# Ikea_Environmental_Sensor.net
KiCad netlist of a schematic drawn in Altium Designer
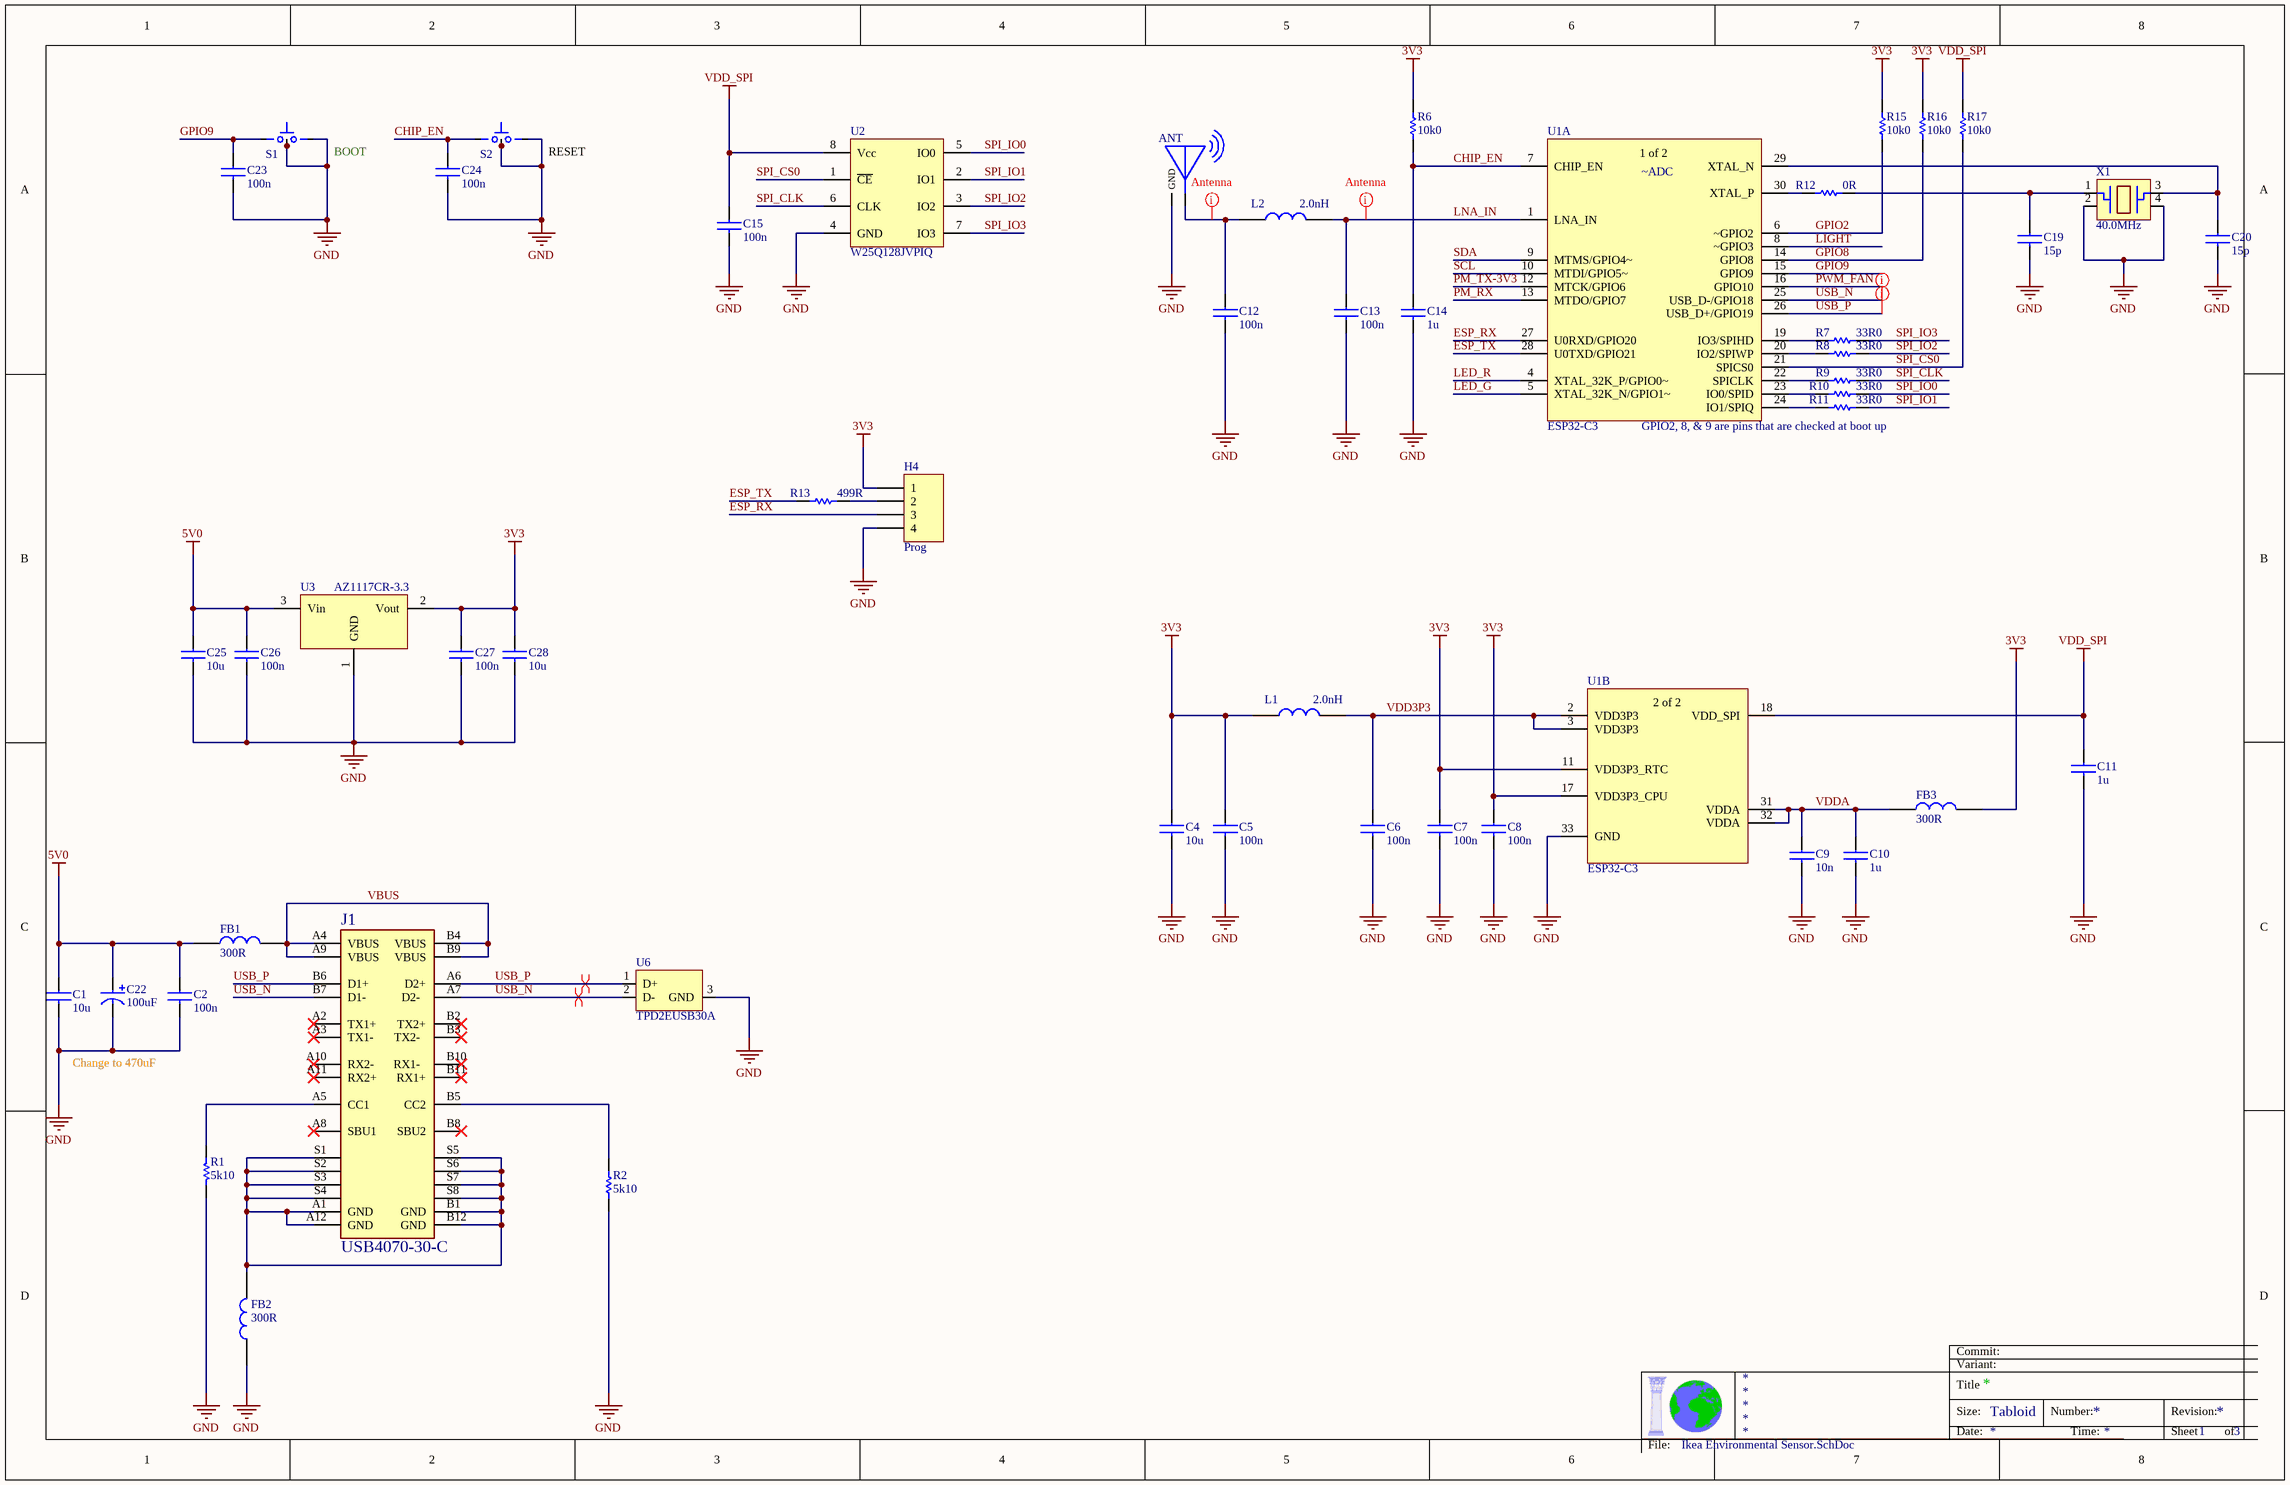
[diagram p0: Ikea Environmental Sensor.SchDoc]

(export (version "E")
  (design (tool "Eeschema 10.0.6"))
  (components
    (comp (ref "ANT")
      (value "PCB Antenna")
      (footprint "MINI-ANT-TYPED-H - Flipped")
      (description "Antenna MIFA 2.4Gig")
      (fields (field (name "MANUFACTURER") "Rainsun") (field (name "LCSC_PART_NUMBER") "C99665"))
      (libsource (lib "GLIB") (part "Antenna_PCB_MIFA"))
    )
    (comp (ref "C1")
      (value "10u")
      (footprint "0603X90")
      (description "Cap, Chip, 10uF, 10V, ± 15%, X5R, 0603")
      (fields (field (name "MANUFACTURER") "NIC") (field (name "JLCPCB_PART_#") "C96446"))
      (libsource (lib "GLIB") (part "C_10u_10V_10_0603_NIC"))
    )
    (comp (ref "C2")
      (value "100n")
      (footprint "C_0402_N")
      (description "Cap, Chip, 100nF, 16V, +/-10%, X7R, 0402")
      (fields (field (name "MANUFACTURER") "NIC") (field (name "JLCPCB_PART_#") "C307331"))
      (libsource (lib "GLIB") (part "C_100n_16V_10_0402_NIC"))
    )
    (comp (ref "C4")
      (value "10u")
      (footprint "0603X90")
      (description "Cap, Chip, 10uF, 10V, ± 15%, X5R, 0603")
      (fields (field (name "MANUFACTURER") "NIC"))
      (libsource (lib "GLIB") (part "C_10u_10V_10_0603_NIC"))
    )
    (comp (ref "C5")
      (value "100n")
      (footprint "C_0402_N")
      (description "Cap, Chip, 100nF, 16V, +/-10%, X7R, 0402")
      (fields (field (name "MANUFACTURER") "NIC"))
      (libsource (lib "GLIB") (part "C_100n_16V_10_0402_NIC"))
    )
    (comp (ref "C6")
      (value "100n")
      (footprint "C_0402_N")
      (description "Cap, Chip, 100nF, 16V, +/-10%, X7R, 0402")
      (fields (field (name "MANUFACTURER") "NIC"))
      (libsource (lib "GLIB") (part "C_100n_16V_10_0402_NIC"))
    )
    (comp (ref "C7")
      (value "100n")
      (footprint "C_0402_N")
      (description "Cap, Chip, 100nF, 16V, +/-10%, X7R, 0402")
      (fields (field (name "MANUFACTURER") "NIC"))
      (libsource (lib "GLIB") (part "C_100n_16V_10_0402_NIC"))
    )
    (comp (ref "C8")
      (value "100n")
      (footprint "C_0402_N")
      (description "Cap, Chip, 100nF, 16V, +/-10%, X7R, 0402")
      (fields (field (name "MANUFACTURER") "NIC"))
      (libsource (lib "GLIB") (part "C_100n_16V_10_0402_NIC"))
    )
    (comp (ref "C9")
      (value "10n")
      (footprint "C_0402_N")
      (description "Cap, Chip, 0.01uF, 25V, 20%, X7R, 0402")
      (fields (field (name "MANUFACTURER") "NIC"))
      (libsource (lib "GLIB") (part "C_10n_25V_20_0402_NIC"))
    )
    (comp (ref "C10")
      (value "1u")
      (footprint "C_0402_N")
      (description "Cap, Chip, 1uF, 10V, 10%, X5R, 0402")
      (fields (field (name "MANUFACTURER") "NIC"))
      (libsource (lib "GLIB") (part "C_1u_10V_10_0402_NIC"))
    )
    (comp (ref "C11")
      (value "1u")
      (footprint "C_0402_N")
      (description "Cap, Chip, 1uF, 10V, 10%, X5R, 0402")
      (fields (field (name "MANUFACTURER") "NIC"))
      (libsource (lib "GLIB") (part "C_1u_10V_10_0402_NIC"))
    )
    (comp (ref "C12")
      (value "100n")
      (footprint "C_0201")
      (description "Cap, Chip, 100nF, 25V, +/-10%, X5R, 0201")
      (fields (field (name "MANUFACTURER") "Murata"))
      (libsource (lib "GLIB") (part "C_100n_25V_10_0201_Murata"))
    )
    (comp (ref "C13")
      (value "100n")
      (footprint "C_0201")
      (description "Cap, Chip, 100nF, 25V, +/-10%, X5R, 0201")
      (fields (field (name "MANUFACTURER") "Murata"))
      (libsource (lib "GLIB") (part "C_100n_25V_10_0201_Murata"))
    )
    (comp (ref "C14")
      (value "1u")
      (footprint "C_0402_N")
      (description "Cap, Chip, 1uF, 10V, 10%, X5R, 0402")
      (fields (field (name "MANUFACTURER") "NIC"))
      (libsource (lib "GLIB") (part "C_1u_10V_10_0402_NIC"))
    )
    (comp (ref "C15")
      (value "100n")
      (footprint "C_0402_N")
      (description "Cap, Chip, 100nF, 16V, +/-10%, X7R, 0402")
      (fields (field (name "MANUFACTURER") "NIC"))
      (libsource (lib "GLIB") (part "C_100n_16V_10_0402_NIC"))
    )
    (comp (ref "C19")
      (value "15p")
      (footprint "C_0402_N")
      (description "Cap, Chip, 15pF, 25V, 10%, NPO 0402")
      (fields (field (name "MANUFACTURER") "NIC"))
      (libsource (lib "GLIB") (part "C_15p_25V_10_0402_NIC"))
    )
    (comp (ref "C20")
      (value "15p")
      (footprint "C_0402_N")
      (description "Cap, Chip, 15pF, 25V, 10%, NPO 0402")
      (fields (field (name "MANUFACTURER") "NIC"))
      (libsource (lib "GLIB") (part "C_15p_25V_10_0402_NIC"))
    )
    (comp (ref "C22")
      (value "100uF")
      (footprint "CAP_6.6x6.6")
      (description "Cap AlEl, 100uF, 35V, 20%, 6.6mm dia.")
      (fields (field (name "MANUFACTURER") "Panasonic") (field (name "Comment") "100uF, 35V"))
      (libsource (lib "GLIB") (part "C_100uF_35V_20_6.6mm_Panasonic"))
    )
    (comp (ref "C23")
      (value "100n")
      (footprint "C_0402_N")
      (description "Cap, Chip, 100nF, 16V, +/-10%, X7R, 0402")
      (fields (field (name "MANUFACTURER") "NIC"))
      (libsource (lib "GLIB") (part "C_100n_16V_10_0402_NIC"))
    )
    (comp (ref "C24")
      (value "100n")
      (footprint "C_0402_N")
      (description "Cap, Chip, 100nF, 16V, +/-10%, X7R, 0402")
      (fields (field (name "MANUFACTURER") "NIC"))
      (libsource (lib "GLIB") (part "C_100n_16V_10_0402_NIC"))
    )
    (comp (ref "C25")
      (value "10u")
      (footprint "0603X90")
      (description "Cap, Chip, 10uF, 10V, ± 15%, X5R, 0603")
      (fields (field (name "MANUFACTURER") "NIC"))
      (libsource (lib "GLIB") (part "C_10u_10V_10_0603_NIC"))
    )
    (comp (ref "C26")
      (value "100n")
      (footprint "C_0402_N")
      (description "Cap, Chip, 100nF, 16V, +/-10%, X7R, 0402")
      (fields (field (name "MANUFACTURER") "NIC"))
      (libsource (lib "GLIB") (part "C_100n_16V_10_0402_NIC"))
    )
    (comp (ref "C27")
      (value "100n")
      (footprint "C_0402_N")
      (description "Cap, Chip, 100nF, 16V, +/-10%, X7R, 0402")
      (fields (field (name "MANUFACTURER") "NIC"))
      (libsource (lib "GLIB") (part "C_100n_16V_10_0402_NIC"))
    )
    (comp (ref "C28")
      (value "10u")
      (footprint "0603X90")
      (description "Cap, Chip, 10uF, 10V, ± 15%, X5R, 0603")
      (fields (field (name "MANUFACTURER") "NIC"))
      (libsource (lib "GLIB") (part "C_10u_10V_10_0603_NIC"))
    )
    (comp (ref "FB1")
      (value "300R")
      (footprint "FB_0402-NIC")
      (description "Ferrite bead,300 ohm@100MHz,0.15 ohm @DC, 1A, 0402")
      (fields (field (name "MANUFACTURER") "NIC"))
      (libsource (lib "GLIB") (part "FB_300R_0402_NIC"))
    )
    (comp (ref "FB2")
      (value "300R")
      (footprint "FB_0402-NIC")
      (description "Ferrite bead,300 ohm@100MHz,0.15 ohm @DC, 1A, 0402")
      (fields (field (name "MANUFACTURER") "NIC"))
      (libsource (lib "GLIB") (part "FB_300R_0402_NIC"))
    )
    (comp (ref "FB3")
      (value "300R")
      (footprint "FB_0402-NIC")
      (description "Ferrite bead,300 ohm@100MHz,0.15 ohm @DC, 1A, 0402")
      (fields (field (name "MANUFACTURER") "NIC"))
      (libsource (lib "GLIB") (part "FB_300R_0402_NIC"))
    )
    (comp (ref "H4")
      (value "Prog")
      (footprint "HDR1X4")
      (description "Header, 4-Pin")
      (libsource (lib "GLIB") (part "Header 4"))
    )
    (comp (ref "J1")
      (value "USB4070-30-C")
      (footprint "USB_C_GCT_USB4070-30-C_REVC5")
      (description "CONN RCPT USB 3.1 Type C Vertical SMT")
      (fields (field (name "MANUFACTURER") "GCT") (field (name "JLCPCB PART #") "C168703"))
      (libsource (lib "GLIB") (part "J_USB_C_REC_SMT_V"))
    )
    (comp (ref "L1")
      (value "2.0nH")
      (footprint "FB_0402-NIC")
      (description "Inductor 2.0nH, +/-0.3nH, LQG15HS2N0S02D, 0402")
      (fields (field (name "MANUFACTURER") "Murata") (field (name "JLCPCB PART #") "C880712"))
      (libsource (lib "GLIB") (part "L_2nH_LQG15HS2N0S02D_0402"))
    )
    (comp (ref "L2")
      (value "2.0nH")
      (footprint "L_0201")
      (description "Inductor 2.0nH, +/-0.1nH, 600mA, 0201")
      (fields (field (name "MANUFACTURER") "Murata"))
      (libsource (lib "GLIB") (part "L_2nH_LQP03TN2N0B02D_0201"))
    )
    (comp (ref "R1")
      (value "5k10")
      (footprint "R_0402-N")
      (description "Resistor, 5.10 kΩ, 1%, 0.06W, 0402")
      (fields (field (name "MANUFACTURER") "NIC") (field (name "JLCPCB_PART_#") "C25905"))
      (libsource (lib "GLIB") (part "R_5k10_60mW_1_0402_NIC"))
    )
    (comp (ref "R2")
      (value "5k10")
      (footprint "R_0402-N")
      (description "Resistor, 5.10 kΩ, 1%, 0.06W, 0402")
      (fields (field (name "MANUFACTURER") "NIC") (field (name "JLCPCB_PART_#") "C25905"))
      (libsource (lib "GLIB") (part "R_5k10_60mW_1_0402_NIC"))
    )
    (comp (ref "R6")
      (value "10k0")
      (footprint "R_0402-N")
      (description "Resistor, 10.0 kΩ, 1%, 0.06W, 0402")
      (fields (field (name "MANUFACTURER") "NIC"))
      (libsource (lib "GLIB") (part "R_10k0_60mW_1_0402_NIC"))
    )
    (comp (ref "R7")
      (value "33R0")
      (footprint "R_0402-N")
      (description "Resistor, 33.0 Ω, 1%, 0.06W, 0402")
      (fields (field (name "MANUFACTURER") "NIC"))
      (libsource (lib "GLIB") (part "R_33R0_60mW_1_0402_NIC"))
    )
    (comp (ref "R8")
      (value "33R0")
      (footprint "R_0402-N")
      (description "Resistor, 33.0 Ω, 1%, 0.06W, 0402")
      (fields (field (name "MANUFACTURER") "NIC"))
      (libsource (lib "GLIB") (part "R_33R0_60mW_1_0402_NIC"))
    )
    (comp (ref "R9")
      (value "33R0")
      (footprint "R_0402-N")
      (description "Resistor, 33.0 Ω, 1%, 0.06W, 0402")
      (fields (field (name "MANUFACTURER") "NIC"))
      (libsource (lib "GLIB") (part "R_33R0_60mW_1_0402_NIC"))
    )
    (comp (ref "R10")
      (value "33R0")
      (footprint "R_0402-N")
      (description "Resistor, 33.0 Ω, 1%, 0.06W, 0402")
      (fields (field (name "MANUFACTURER") "NIC"))
      (libsource (lib "GLIB") (part "R_33R0_60mW_1_0402_NIC"))
    )
    (comp (ref "R11")
      (value "33R0")
      (footprint "R_0402-N")
      (description "Resistor, 33.0 Ω, 1%, 0.06W, 0402")
      (fields (field (name "MANUFACTURER") "NIC"))
      (libsource (lib "GLIB") (part "R_33R0_60mW_1_0402_NIC"))
    )
    (comp (ref "R12")
      (value "0R")
      (footprint "R_0402-N")
      (description "Resistor, 0 Ω, 1%, 0.06W, 0402")
      (fields (field (name "MANUFACTURER") "NIC"))
      (libsource (lib "GLIB") (part "R_0R00_60mW_1_0402_NIC"))
    )
    (comp (ref "R13")
      (value "499R")
      (footprint "R_0402-N")
      (description "Resistor, 499 Ω, 1%, 0.06W, 0402")
      (fields (field (name "MANUFACTURER") "NIC"))
      (libsource (lib "GLIB") (part "R_499R_60mW_1_0402_NIC"))
    )
    (comp (ref "R15")
      (value "10k0")
      (footprint "R_0402-N")
      (description "Resistor, 10.0 kΩ, 1%, 0.06W, 0402")
      (fields (field (name "MANUFACTURER") "NIC"))
      (libsource (lib "GLIB") (part "R_10k0_60mW_1_0402_NIC"))
    )
    (comp (ref "R16")
      (value "10k0")
      (footprint "R_0402-N")
      (description "Resistor, 10.0 kΩ, 1%, 0.06W, 0402")
      (fields (field (name "MANUFACTURER") "NIC"))
      (libsource (lib "GLIB") (part "R_10k0_60mW_1_0402_NIC"))
    )
    (comp (ref "R17")
      (value "10k0")
      (footprint "R_0402-N")
      (description "Resistor, 10.0 kΩ, 1%, 0.06W, 0402")
      (fields (field (name "MANUFACTURER") "NIC"))
      (libsource (lib "GLIB") (part "R_10k0_60mW_1_0402_NIC"))
    )
    (comp (ref "S1")
      (value "BOOT")
      (footprint "SW_122514")
      (description "Side Actuated Button R/A")
      (fields (field (name "MANUFACTURER") "HYP") (field (name "JLCPCB PART #") "C319377"))
      (libsource (lib "GLIB") (part "SW_Side Actuated Button R/A"))
    )
    (comp (ref "S2")
      (value "RESET")
      (footprint "SW_122514")
      (description "Side Actuated Button R/A")
      (fields (field (name "MANUFACTURER") "HYP") (field (name "JLCPCB PART #") "C319377"))
      (libsource (lib "GLIB") (part "SW_Side Actuated Button R/A"))
    )
    (comp (ref "U1")
      (value "ESP32-C3")
      (footprint "QFN-32_5x5")
      (description "IC, ESP32-C3, 160MHz RISC-V Single Core, QFN32")
      (fields (field (name "MANUFACTURER") "Espressif Systems"))
      (libsource (lib "GLIB") (part "U_ESP32-C3_QFN32"))
    )
    (comp (ref "U2")
      (value "W25Q128JVPIQ")
      (footprint "WSON_8")
      (description "IC, Flash Memory 128Mb (16Mkx8), 3.3V, WSON8-5x6")
      (fields (field (name "MANUFACTURER") "Winbond") (field (name "JLCPCB PART #") "C2803379"))
      (libsource (lib "GLIB") (part "U_W25Q128JVPIQ_WSON8"))
    )
    (comp (ref "U3")
      (value "AZ1117CR-3.3")
      (footprint "SOT89-150P410X160-3N")
      (description "IC, CONV DC/DC LDO 3.3V, 15V In 1A, SOT89-3")
      (fields (field (name "MANUFACTURER") "Diodes Inc") (field (name "JLCPCB PART #") "C347256"))
      (libsource (lib "GLIB") (part "U_AZ1117CR-3.3TRG1_SOT89-3"))
    )
    (comp (ref "U6")
      (value "TPD2EUSB30A")
      (footprint "DRT3")
      (description "2 Channel ESD for USB 3.0")
      (fields (field (name "MANUFACTURER") "Texas Instruments") (field (name "JLCPCB_PART_#") "C94934"))
      (libsource (lib "GLIB") (part "U_TPD2EUSB30A-SOT_DRT-3"))
    )
    (comp (ref "X1")
      (value "40.0MHz")
      (description "X-tal, 40.000MHz, Cl=4pF, +-10ppm, 3.2x2.5")
      (fields (field (name "MANUFACTURER") "ABRACON Co") (field (name "JLCPCB PART #") "C90924"))
      (libsource (lib "GLIB") (part "X_40.000MHZ_12pF_3225"))
    )
  )
  (nets
    (net (code "1") (name "/CHIP_EN") (class "Default")
      (node (ref "C14") (pin "1") (pinfunction "1_1") (pintype "passive"))
      (node (ref "C24") (pin "1") (pinfunction "1_1") (pintype "passive"))
      (node (ref "R6") (pin "1") (pinfunction "1_1") (pintype "passive"))
      (node (ref "S2") (pin "1") (pinfunction "A_1") (pintype "passive"))
      (node (ref "U1") (pin "7") (pinfunction "CHIP_EN_7") (pintype "passive"))
    )
    (net (code "2") (name "/ESP_RX") (class "Default")
      (node (ref "H4") (pin "3") (pinfunction "3_3") (pintype "passive"))
      (node (ref "U1") (pin "27") (pinfunction "U0RXD/GPIO20_27") (pintype "passive"))
    )
    (net (code "3") (name "/ESP_TX") (class "Default")
      (node (ref "R13") (pin "1") (pinfunction "1_1") (pintype "passive"))
      (node (ref "U1") (pin "28") (pinfunction "U0TXD/GPIO21_28") (pintype "passive"))
    )
    (net (code "4") (name "/GPIO2") (class "Default")
      (node (ref "R15") (pin "1") (pinfunction "1_1") (pintype "passive"))
      (node (ref "U1") (pin "6") (pinfunction "~GPIO2_6") (pintype "passive"))
    )
    (net (code "5") (name "/GPIO8") (class "Default")
      (node (ref "R16") (pin "1") (pinfunction "1_1") (pintype "passive"))
      (node (ref "U1") (pin "14") (pinfunction "GPIO8_14") (pintype "passive"))
    )
    (net (code "6") (name "/GPIO9") (class "Default")
      (node (ref "C23") (pin "1") (pinfunction "1_1") (pintype "passive"))
      (node (ref "S1") (pin "1") (pinfunction "A_1") (pintype "passive"))
      (node (ref "U1") (pin "15") (pinfunction "GPIO9_15") (pintype "passive"))
    )
    (net (code "7") (name "/LED_G") (class "Default")
      (node (ref "U1") (pin "5") (pinfunction "XTAL_32K_N/GPIO1~_5") (pintype "passive"))
    )
    (net (code "8") (name "/LED_R") (class "Default")
      (node (ref "U1") (pin "4") (pinfunction "XTAL_32K_P/GPIO0~_4") (pintype "passive"))
    )
    (net (code "9") (name "/LIGHT") (class "Default")
      (node (ref "U1") (pin "8") (pinfunction "~GPIO3_8") (pintype "passive"))
    )
    (net (code "10") (name "/LNA_IN") (class "Default")
      (node (ref "C13") (pin "1") (pinfunction "1_1") (pintype "passive"))
      (node (ref "L2") (pin "2") (pinfunction "2_2") (pintype "passive"))
      (node (ref "U1") (pin "1") (pinfunction "LNA_IN_1") (pintype "passive"))
    )
    (net (code "11") (name "/PM_RX") (class "Default")
      (node (ref "U1") (pin "13") (pinfunction "MTDO/GPIO7_13") (pintype "passive"))
    )
    (net (code "12") (name "/PM_TX-3V3") (class "Default")
      (node (ref "U1") (pin "12") (pinfunction "MTCK/GPIO6_12") (pintype "passive"))
    )
    (net (code "13") (name "/PWM_FAN") (class "Default")
      (node (ref "U1") (pin "16") (pinfunction "GPIO10_16") (pintype "passive"))
    )
    (net (code "14") (name "/SCL") (class "Default")
      (node (ref "U1") (pin "10") (pinfunction "MTDI/GPIO5~_10") (pintype "passive"))
    )
    (net (code "15") (name "/SDA") (class "Default")
      (node (ref "U1") (pin "9") (pinfunction "MTMS/GPIO4~_9") (pintype "passive"))
    )
    (net (code "16") (name "/SPI_CLK") (class "Default")
      (node (ref "R9") (pin "2") (pinfunction "2_2") (pintype "passive"))
      (node (ref "U2") (pin "6") (pinfunction "CLK_6") (pintype "passive"))
    )
    (net (code "17") (name "/SPI_CS0") (class "Default")
      (node (ref "R17") (pin "1") (pinfunction "1_1") (pintype "passive"))
      (node (ref "U1") (pin "21") (pinfunction "SPICS0_21") (pintype "passive"))
      (node (ref "U2") (pin "1") (pinfunction "~{CE}_1") (pintype "passive"))
    )
    (net (code "18") (name "/SPI_IO0") (class "Default")
      (node (ref "R10") (pin "2") (pinfunction "2_2") (pintype "passive"))
      (node (ref "U2") (pin "5") (pinfunction "IO0_5") (pintype "passive"))
    )
    (net (code "19") (name "/SPI_IO1") (class "Default")
      (node (ref "R11") (pin "2") (pinfunction "2_2") (pintype "passive"))
      (node (ref "U2") (pin "2") (pinfunction "IO1_2") (pintype "passive"))
    )
    (net (code "20") (name "/SPI_IO2") (class "Default")
      (node (ref "R8") (pin "2") (pinfunction "2_2") (pintype "passive"))
      (node (ref "U2") (pin "3") (pinfunction "IO2_3") (pintype "passive"))
    )
    (net (code "21") (name "/SPI_IO3") (class "Default")
      (node (ref "R7") (pin "2") (pinfunction "2_2") (pintype "passive"))
      (node (ref "U2") (pin "7") (pinfunction "IO3_7") (pintype "passive"))
    )
    (net (code "22") (name "/USB_N") (class "Default")
      (node (ref "J1") (pin "A7") (pinfunction "D2-_A7") (pintype "passive"))
      (node (ref "J1") (pin "B7") (pinfunction "D1-_B7") (pintype "passive"))
      (node (ref "U1") (pin "25") (pinfunction "USB_D-/GPIO18_25") (pintype "passive"))
      (node (ref "U6") (pin "2") (pinfunction "D-_2") (pintype "passive"))
    )
    (net (code "23") (name "/USB_P") (class "Default")
      (node (ref "J1") (pin "A6") (pinfunction "D2+_A6") (pintype "passive"))
      (node (ref "J1") (pin "B6") (pinfunction "D1+_B6") (pintype "passive"))
      (node (ref "U1") (pin "26") (pinfunction "USB_D+/GPIO19_26") (pintype "passive"))
      (node (ref "U6") (pin "1") (pinfunction "D+_1") (pintype "passive"))
    )
    (net (code "24") (name "/VBUS") (class "Default")
      (node (ref "FB1") (pin "2") (pinfunction "2_2") (pintype "passive"))
      (node (ref "J1") (pin "A4") (pinfunction "VBUS_A4") (pintype "power_in"))
      (node (ref "J1") (pin "A9") (pinfunction "VBUS_A9") (pintype "power_in"))
      (node (ref "J1") (pin "B4") (pinfunction "VBUS_B4") (pintype "power_in"))
      (node (ref "J1") (pin "B9") (pinfunction "VBUS_B9") (pintype "power_in"))
    )
    (net (code "25") (name "/VDD3P3") (class "Default")
      (node (ref "C6") (pin "1") (pinfunction "1_1") (pintype "passive"))
      (node (ref "L1") (pin "2") (pinfunction "2_2") (pintype "passive"))
      (node (ref "U1") (pin "2") (pinfunction "VDD3P3_2") (pintype "power_in"))
      (node (ref "U1") (pin "3") (pinfunction "VDD3P3_3") (pintype "power_in"))
    )
    (net (code "26") (name "/VDDA") (class "Default")
      (node (ref "C10") (pin "1") (pinfunction "1_1") (pintype "passive"))
      (node (ref "C9") (pin "1") (pinfunction "1_1") (pintype "passive"))
      (node (ref "FB3") (pin "1") (pinfunction "1_1") (pintype "passive"))
      (node (ref "U1") (pin "31") (pinfunction "VDDA_31") (pintype "power_in"))
      (node (ref "U1") (pin "32") (pinfunction "VDDA_32") (pintype "power_in"))
    )
    (net (code "27") (name "3V3") (class "Default")
      (node (ref "C27") (pin "1") (pinfunction "1_1") (pintype "passive"))
      (node (ref "C28") (pin "1") (pinfunction "1_1") (pintype "passive"))
      (node (ref "C4") (pin "1") (pinfunction "1_1") (pintype "passive"))
      (node (ref "C5") (pin "1") (pinfunction "1_1") (pintype "passive"))
      (node (ref "C7") (pin "1") (pinfunction "1_1") (pintype "passive"))
      (node (ref "C8") (pin "1") (pinfunction "1_1") (pintype "passive"))
      (node (ref "FB3") (pin "2") (pinfunction "2_2") (pintype "passive"))
      (node (ref "H4") (pin "1") (pinfunction "1_1") (pintype "passive"))
      (node (ref "L1") (pin "1") (pinfunction "1_1") (pintype "passive"))
      (node (ref "R15") (pin "2") (pinfunction "2_2") (pintype "passive"))
      (node (ref "R16") (pin "2") (pinfunction "2_2") (pintype "passive"))
      (node (ref "R6") (pin "2") (pinfunction "2_2") (pintype "passive"))
      (node (ref "U1") (pin "11") (pinfunction "VDD3P3_RTC_11") (pintype "power_in"))
      (node (ref "U1") (pin "17") (pinfunction "VDD3P3_CPU_17") (pintype "power_in"))
      (node (ref "U3") (pin "2") (pinfunction "Vout_2") (pintype "power_in"))
    )
    (net (code "28") (name "5V0") (class "Default")
      (node (ref "C1") (pin "1") (pinfunction "1_1") (pintype "passive"))
      (node (ref "C2") (pin "1") (pinfunction "1_1") (pintype "passive"))
      (node (ref "C22") (pin "1") (pinfunction "1_1") (pintype "passive"))
      (node (ref "C25") (pin "1") (pinfunction "1_1") (pintype "passive"))
      (node (ref "C26") (pin "1") (pinfunction "1_1") (pintype "passive"))
      (node (ref "FB1") (pin "1") (pinfunction "1_1") (pintype "passive"))
      (node (ref "U3") (pin "3") (pinfunction "Vin_3") (pintype "power_in"))
    )
    (net (code "29") (name "GND") (class "Default")
      (node (ref "ANT") (pin "2") (pinfunction "GND_2") (pintype "passive"))
      (node (ref "C1") (pin "2") (pinfunction "2_2") (pintype "passive"))
      (node (ref "C10") (pin "2") (pinfunction "2_2") (pintype "passive"))
      (node (ref "C11") (pin "2") (pinfunction "2_2") (pintype "passive"))
      (node (ref "C12") (pin "2") (pinfunction "2_2") (pintype "passive"))
      (node (ref "C13") (pin "2") (pinfunction "2_2") (pintype "passive"))
      (node (ref "C14") (pin "2") (pinfunction "2_2") (pintype "passive"))
      (node (ref "C15") (pin "2") (pinfunction "2_2") (pintype "passive"))
      (node (ref "C19") (pin "2") (pinfunction "2_2") (pintype "passive"))
      (node (ref "C2") (pin "2") (pinfunction "2_2") (pintype "passive"))
      (node (ref "C20") (pin "2") (pinfunction "2_2") (pintype "passive"))
      (node (ref "C22") (pin "2") (pinfunction "2_2") (pintype "passive"))
      (node (ref "C23") (pin "2") (pinfunction "2_2") (pintype "passive"))
      (node (ref "C24") (pin "2") (pinfunction "2_2") (pintype "passive"))
      (node (ref "C25") (pin "2") (pinfunction "2_2") (pintype "passive"))
      (node (ref "C26") (pin "2") (pinfunction "2_2") (pintype "passive"))
      (node (ref "C27") (pin "2") (pinfunction "2_2") (pintype "passive"))
      (node (ref "C28") (pin "2") (pinfunction "2_2") (pintype "passive"))
      (node (ref "C4") (pin "2") (pinfunction "2_2") (pintype "passive"))
      (node (ref "C5") (pin "2") (pinfunction "2_2") (pintype "passive"))
      (node (ref "C6") (pin "2") (pinfunction "2_2") (pintype "passive"))
      (node (ref "C7") (pin "2") (pinfunction "2_2") (pintype "passive"))
      (node (ref "C8") (pin "2") (pinfunction "2_2") (pintype "passive"))
      (node (ref "C9") (pin "2") (pinfunction "2_2") (pintype "passive"))
      (node (ref "FB2") (pin "1") (pinfunction "1_1") (pintype "passive"))
      (node (ref "H4") (pin "4") (pinfunction "4_4") (pintype "passive"))
      (node (ref "R1") (pin "1") (pinfunction "1_1") (pintype "passive"))
      (node (ref "R2") (pin "1") (pinfunction "1_1") (pintype "passive"))
      (node (ref "S1") (pin "2") (pinfunction "B_2") (pintype "passive"))
      (node (ref "S1") (pin "3") (pinfunction "3_3") (pintype "passive"))
      (node (ref "S1") (pin "4") (pinfunction "4_4") (pintype "passive"))
      (node (ref "S2") (pin "2") (pinfunction "B_2") (pintype "passive"))
      (node (ref "S2") (pin "3") (pinfunction "3_3") (pintype "passive"))
      (node (ref "S2") (pin "4") (pinfunction "4_4") (pintype "passive"))
      (node (ref "U1") (pin "33") (pinfunction "GND_33") (pintype "power_in"))
      (node (ref "U2") (pin "4") (pinfunction "GND_4") (pintype "power_in"))
      (node (ref "U3") (pin "1") (pinfunction "GND_1") (pintype "power_in"))
      (node (ref "U6") (pin "3") (pinfunction "GND_3") (pintype "power_in"))
      (node (ref "X1") (pin "2") (pinfunction "GND_2") (pintype "passive"))
      (node (ref "X1") (pin "4") (pinfunction "GND_4") (pintype "passive"))
    )
    (net (code "30") (name "Net-(ANT-Pad1)") (class "Default")
      (node (ref "ANT") (pin "1") (pintype "passive"))
      (node (ref "C12") (pin "1") (pinfunction "1_1") (pintype "passive"))
      (node (ref "L2") (pin "1") (pinfunction "1_1") (pintype "passive"))
    )
    (net (code "31") (name "Net-(C19-Pad1)") (class "Default")
      (node (ref "C19") (pin "1") (pinfunction "1_1") (pintype "passive"))
      (node (ref "R12") (pin "2") (pinfunction "2_2") (pintype "passive"))
      (node (ref "X1") (pin "1") (pinfunction "1_1") (pintype "passive"))
    )
    (net (code "32") (name "Net-(FB2-Pad2)") (class "Default")
      (node (ref "FB2") (pin "2") (pinfunction "2_2") (pintype "passive"))
      (node (ref "J1") (pin "A1") (pinfunction "GND_A1") (pintype "power_in"))
      (node (ref "J1") (pin "A12") (pinfunction "GND_A12") (pintype "power_in"))
      (node (ref "J1") (pin "B1") (pinfunction "GND_B1") (pintype "power_in"))
      (node (ref "J1") (pin "B12") (pinfunction "GND_B12") (pintype "power_in"))
      (node (ref "J1") (pin "S1") (pinfunction "Shield_S1") (pintype "passive"))
      (node (ref "J1") (pin "S2") (pinfunction "Shield_S2") (pintype "passive"))
      (node (ref "J1") (pin "S3") (pinfunction "Shield_S3") (pintype "passive"))
      (node (ref "J1") (pin "S4") (pinfunction "Shield_S4") (pintype "passive"))
      (node (ref "J1") (pin "S5") (pinfunction "Shield_S5") (pintype "passive"))
      (node (ref "J1") (pin "S6") (pinfunction "Shield_S6") (pintype "passive"))
      (node (ref "J1") (pin "S7") (pinfunction "Shield_S7") (pintype "passive"))
      (node (ref "J1") (pin "S8") (pinfunction "Shield_S8") (pintype "passive"))
    )
    (net (code "33") (name "Net-(H4-Pad2)") (class "Default")
      (node (ref "H4") (pin "2") (pinfunction "2_2") (pintype "passive"))
      (node (ref "R13") (pin "2") (pinfunction "2_2") (pintype "passive"))
    )
    (net (code "34") (name "Net-(J1-CC1)") (class "Default")
      (node (ref "J1") (pin "A5") (pinfunction "CC1_A5") (pintype "passive"))
      (node (ref "R1") (pin "2") (pinfunction "2_2") (pintype "passive"))
    )
    (net (code "35") (name "Net-(J1-CC2)") (class "Default")
      (node (ref "J1") (pin "B5") (pinfunction "CC2_B5") (pintype "passive"))
      (node (ref "R2") (pin "2") (pinfunction "2_2") (pintype "passive"))
    )
    (net (code "36") (name "Net-(U1A-IO0{slash}SPID)") (class "Default")
      (node (ref "R10") (pin "1") (pinfunction "1_1") (pintype "passive"))
      (node (ref "U1") (pin "23") (pinfunction "IO0/SPID_23") (pintype "passive"))
    )
    (net (code "37") (name "Net-(U1A-IO1{slash}SPIQ)") (class "Default")
      (node (ref "R11") (pin "1") (pinfunction "1_1") (pintype "passive"))
      (node (ref "U1") (pin "24") (pinfunction "IO1/SPIQ_24") (pintype "passive"))
    )
    (net (code "38") (name "Net-(U1A-IO2{slash}SPIWP)") (class "Default")
      (node (ref "R8") (pin "1") (pinfunction "1_1") (pintype "passive"))
      (node (ref "U1") (pin "20") (pinfunction "IO2/SPIWP_20") (pintype "passive"))
    )
    (net (code "39") (name "Net-(U1A-IO3{slash}SPIHD)") (class "Default")
      (node (ref "R7") (pin "1") (pinfunction "1_1") (pintype "passive"))
      (node (ref "U1") (pin "19") (pinfunction "IO3/SPIHD_19") (pintype "passive"))
    )
    (net (code "40") (name "Net-(U1A-SPICLK)") (class "Default")
      (node (ref "R9") (pin "1") (pinfunction "1_1") (pintype "passive"))
      (node (ref "U1") (pin "22") (pinfunction "SPICLK_22") (pintype "passive"))
    )
    (net (code "41") (name "Net-(U1A-XTAL_N)") (class "Default")
      (node (ref "C20") (pin "1") (pinfunction "1_1") (pintype "passive"))
      (node (ref "U1") (pin "29") (pinfunction "XTAL_N_29") (pintype "passive"))
      (node (ref "X1") (pin "3") (pinfunction "3_3") (pintype "passive"))
    )
    (net (code "42") (name "Net-(U1A-XTAL_P)") (class "Default")
      (node (ref "R12") (pin "1") (pinfunction "1_1") (pintype "passive"))
      (node (ref "U1") (pin "30") (pinfunction "XTAL_P_30") (pintype "passive"))
    )
    (net (code "43") (name "VDD_SPI") (class "Default")
      (node (ref "C11") (pin "1") (pinfunction "1_1") (pintype "passive"))
      (node (ref "C15") (pin "1") (pinfunction "1_1") (pintype "passive"))
      (node (ref "R17") (pin "2") (pinfunction "2_2") (pintype "passive"))
      (node (ref "U1") (pin "18") (pinfunction "VDD_SPI_18") (pintype "power_in"))
      (node (ref "U2") (pin "8") (pinfunction "Vcc_8") (pintype "power_in"))
    )
    (net (code "44") (name "unconnected-(J1-RX1+-PadB11)") (class "Default")
      (node (ref "J1") (pin "B11") (pinfunction "RX1+_B11") (pintype "passive+no_connect"))
    )
    (net (code "45") (name "unconnected-(J1-RX1--PadB10)") (class "Default")
      (node (ref "J1") (pin "B10") (pinfunction "RX1-_B10") (pintype "passive+no_connect"))
    )
    (net (code "46") (name "unconnected-(J1-RX2+-PadA11)") (class "Default")
      (node (ref "J1") (pin "A11") (pinfunction "RX2+_A11") (pintype "passive+no_connect"))
    )
    (net (code "47") (name "unconnected-(J1-RX2--PadA10)") (class "Default")
      (node (ref "J1") (pin "A10") (pinfunction "RX2-_A10") (pintype "passive+no_connect"))
    )
    (net (code "48") (name "unconnected-(J1-SBU1-PadA8)") (class "Default")
      (node (ref "J1") (pin "A8") (pinfunction "SBU1_A8") (pintype "passive+no_connect"))
    )
    (net (code "49") (name "unconnected-(J1-SBU2-PadB8)") (class "Default")
      (node (ref "J1") (pin "B8") (pinfunction "SBU2_B8") (pintype "passive+no_connect"))
    )
    (net (code "50") (name "unconnected-(J1-TX1+-PadA2)") (class "Default")
      (node (ref "J1") (pin "A2") (pinfunction "TX1+_A2") (pintype "passive+no_connect"))
    )
    (net (code "51") (name "unconnected-(J1-TX1--PadA3)") (class "Default")
      (node (ref "J1") (pin "A3") (pinfunction "TX1-_A3") (pintype "passive+no_connect"))
    )
    (net (code "52") (name "unconnected-(J1-TX2+-PadB2)") (class "Default")
      (node (ref "J1") (pin "B2") (pinfunction "TX2+_B2") (pintype "passive+no_connect"))
    )
    (net (code "53") (name "unconnected-(J1-TX2--PadB3)") (class "Default")
      (node (ref "J1") (pin "B3") (pinfunction "TX2-_B3") (pintype "passive+no_connect"))
    )
  )
)
